# osd_carrier.net
KiCad netlist of a schematic drawn in EAGLE
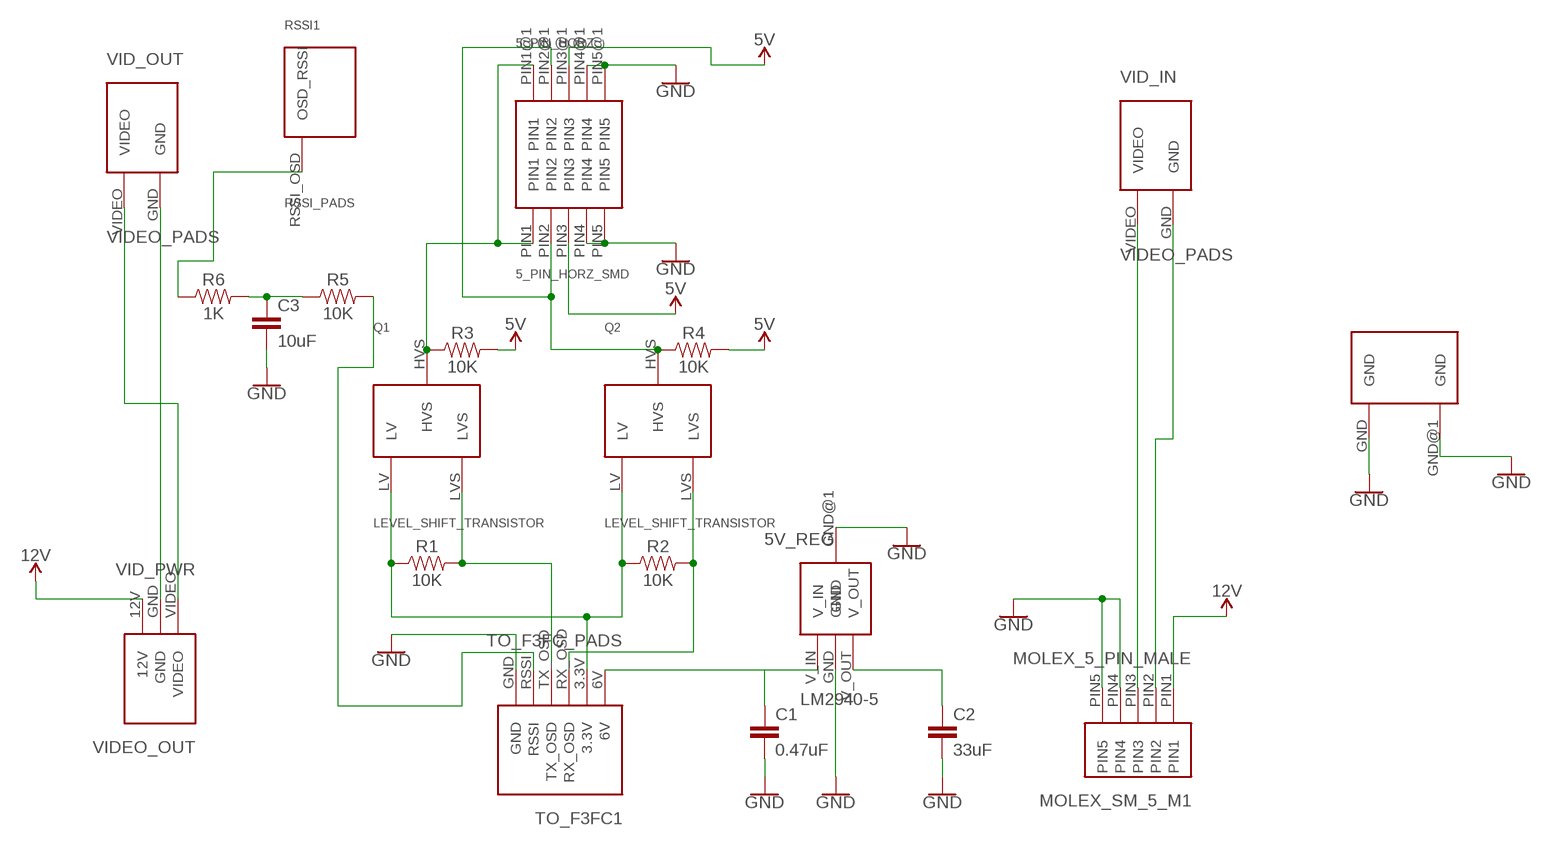
[diagram p0: schematic, sheet 1]

(export (version "E")
  (design (tool "Eeschema 10.0.6"))
  (components
    (comp (ref "5V_REG")
      (value "LM2940-5")
      (footprint "eagle-import:LM2940-5")
      (libsource (lib "eagle-import") (part "LM2940-5"))
    )
    (comp (ref "5_PIN_HORZ")
      (value "5_PIN_HORZ_SMD")
      (footprint "eagle-import:5_PIN_HORZ_SMD")
      (libsource (lib "eagle-import") (part "5_PIN_HORZ_SMD"))
    )
    (comp (ref "ANCHOR1")
      (value "ANCHOR")
      (footprint "eagle-import:ANCHOR")
      (libsource (lib "eagle-import") (part "ANCHOR"))
    )
    (comp (ref "C1")
      (value "0.47uF")
      (footprint "eagle-import:0805")
      (libsource (lib "eagle-import") (part "0.33UF/330NF-0805-50V-10%"))
    )
    (comp (ref "C2")
      (value "33uF")
      (footprint "eagle-import:0805")
      (libsource (lib "eagle-import") (part "0.33UF/330NF-0805-50V-10%"))
    )
    (comp (ref "C3")
      (value "10uF")
      (footprint "eagle-import:0805")
      (libsource (lib "eagle-import") (part "10UF-0805-10V-10%"))
    )
    (comp (ref "MOLEX_SM_5_M1")
      (value "MOLEX_5_PIN_MALE")
      (footprint "eagle-import:MOLEX_5_PIN_MALE")
      (libsource (lib "eagle-import") (part "MOLEX_5_PIN_MALE"))
    )
    (comp (ref "Q1")
      (value "LEVEL_SHIFT_TRANSISTOR")
      (footprint "eagle-import:LEVEL_SHIFT_TRANSISTOR")
      (libsource (lib "eagle-import") (part "LEVEL_SHIFT_TRANSISTOR"))
    )
    (comp (ref "Q2")
      (value "LEVEL_SHIFT_TRANSISTOR")
      (footprint "eagle-import:LEVEL_SHIFT_TRANSISTOR")
      (libsource (lib "eagle-import") (part "LEVEL_SHIFT_TRANSISTOR"))
    )
    (comp (ref "R1")
      (value "10K")
      (footprint "eagle-import:0603")
      (libsource (lib "eagle-import") (part "1OHM-0603-1/10W-1%"))
    )
    (comp (ref "R2")
      (value "10K")
      (footprint "eagle-import:0603")
      (libsource (lib "eagle-import") (part "1OHM-0603-1/10W-1%"))
    )
    (comp (ref "R3")
      (value "10K")
      (footprint "eagle-import:0603")
      (libsource (lib "eagle-import") (part "1OHM-0603-1/10W-1%"))
    )
    (comp (ref "R4")
      (value "10K")
      (footprint "eagle-import:0603")
      (libsource (lib "eagle-import") (part "1OHM-0603-1/10W-1%"))
    )
    (comp (ref "R5")
      (value "10K")
      (footprint "eagle-import:0603")
      (libsource (lib "eagle-import") (part "1OHM-0603-1/10W-1%"))
    )
    (comp (ref "R6")
      (value "1K")
      (footprint "eagle-import:0603")
      (libsource (lib "eagle-import") (part "1OHM-0603-1/10W-1%"))
    )
    (comp (ref "RSSI1")
      (value "RSSI_PADS")
      (footprint "eagle-import:RSSI_PADS")
      (libsource (lib "eagle-import") (part "RSSI_PADS"))
    )
    (comp (ref "TO_F3FC1")
      (value "TO_F3FC_PADS")
      (footprint "eagle-import:TO_F3FC_PADS")
      (libsource (lib "eagle-import") (part "TO_F3FC_PADS"))
    )
    (comp (ref "VIDEO_OUT")
      (value "VID_PWR")
      (footprint "eagle-import:VID_PWR")
      (libsource (lib "eagle-import") (part "VID_PWR"))
    )
    (comp (ref "VID_IN")
      (value "VIDEO_PADS")
      (footprint "eagle-import:VIDEO_PADS")
      (libsource (lib "eagle-import") (part "VIDEO_PADS"))
    )
    (comp (ref "VID_OUT")
      (value "VIDEO_PADS")
      (footprint "eagle-import:VIDEO_PADS")
      (libsource (lib "eagle-import") (part "VIDEO_PADS"))
    )
  )
  (nets
    (net (code "1") (name "5V") (class "Default")
      (node (ref "5V_REG") (pin "V_OUT") (pinfunction "V_OUT_V_OUT") (pintype "bidirectional"))
      (node (ref "5_PIN_HORZ") (pin "PIN3") (pinfunction "PIN3_PIN3") (pintype "bidirectional"))
      (node (ref "5_PIN_HORZ") (pin "PIN3@1") (pinfunction "PIN3_PIN3@1") (pintype "bidirectional"))
      (node (ref "C2") (pin "1") (pinfunction "1_1") (pintype "passive"))
      (node (ref "R3") (pin "2") (pinfunction "2_2") (pintype "passive"))
      (node (ref "R4") (pin "2") (pinfunction "2_2") (pintype "passive"))
    )
    (net (code "2") (name "12V") (class "Default")
      (node (ref "MOLEX_SM_5_M1") (pin "PIN1") (pinfunction "PIN1_PIN1") (pintype "bidirectional"))
      (node (ref "VIDEO_OUT") (pin "12V") (pinfunction "12V_12V") (pintype "bidirectional"))
    )
    (net (code "3") (name "GND") (class "Default")
      (node (ref "5V_REG") (pin "GND") (pinfunction "GND_GND") (pintype "bidirectional"))
      (node (ref "5V_REG") (pin "GND@1") (pinfunction "GND_GND@1") (pintype "bidirectional"))
      (node (ref "5_PIN_HORZ") (pin "PIN4") (pinfunction "PIN4_PIN4") (pintype "bidirectional"))
      (node (ref "5_PIN_HORZ") (pin "PIN4@1") (pinfunction "PIN4_PIN4@1") (pintype "bidirectional"))
      (node (ref "5_PIN_HORZ") (pin "PIN5") (pinfunction "PIN5_PIN5") (pintype "bidirectional"))
      (node (ref "5_PIN_HORZ") (pin "PIN5@1") (pinfunction "PIN5_PIN5@1") (pintype "bidirectional"))
      (node (ref "ANCHOR1") (pin "GND") (pinfunction "GND_GND") (pintype "bidirectional"))
      (node (ref "ANCHOR1") (pin "GND@1") (pinfunction "GND_GND@1") (pintype "bidirectional"))
      (node (ref "C1") (pin "2") (pinfunction "2_2") (pintype "passive"))
      (node (ref "C2") (pin "2") (pinfunction "2_2") (pintype "passive"))
      (node (ref "C3") (pin "2") (pinfunction "2_2") (pintype "passive"))
      (node (ref "MOLEX_SM_5_M1") (pin "PIN2") (pinfunction "PIN2_PIN2") (pintype "bidirectional"))
      (node (ref "MOLEX_SM_5_M1") (pin "PIN4") (pinfunction "PIN4_PIN4") (pintype "bidirectional"))
      (node (ref "MOLEX_SM_5_M1") (pin "PIN5") (pinfunction "PIN5_PIN5") (pintype "bidirectional"))
      (node (ref "TO_F3FC1") (pin "GND") (pinfunction "GND_GND") (pintype "bidirectional"))
      (node (ref "VIDEO_OUT") (pin "GND") (pinfunction "GND_GND") (pintype "bidirectional"))
      (node (ref "VID_IN") (pin "GND") (pinfunction "GND_GND") (pintype "bidirectional"))
      (node (ref "VID_OUT") (pin "GND") (pinfunction "GND_GND") (pintype "bidirectional"))
    )
    (net (code "4") (name "Net-(5V_REG-PadV_IN)") (class "Default")
      (node (ref "5V_REG") (pin "V_IN") (pinfunction "V_IN_V_IN") (pintype "bidirectional"))
      (node (ref "C1") (pin "1") (pinfunction "1_1") (pintype "passive"))
      (node (ref "TO_F3FC1") (pin "6V") (pinfunction "6V_6V") (pintype "bidirectional"))
    )
    (net (code "5") (name "Net-(5_PIN_HORZ-PIN1-PadPIN1@1)") (class "Default")
      (node (ref "5_PIN_HORZ") (pin "PIN1") (pinfunction "PIN1_PIN1") (pintype "bidirectional"))
      (node (ref "5_PIN_HORZ") (pin "PIN1@1") (pinfunction "PIN1_PIN1@1") (pintype "bidirectional"))
      (node (ref "Q1") (pin "HVS") (pinfunction "HVS_HVS") (pintype "bidirectional"))
      (node (ref "R3") (pin "1") (pinfunction "1_1") (pintype "passive"))
    )
    (net (code "6") (name "Net-(5_PIN_HORZ-PIN2-PadPIN2@1)") (class "Default")
      (node (ref "5_PIN_HORZ") (pin "PIN2") (pinfunction "PIN2_PIN2") (pintype "bidirectional"))
      (node (ref "5_PIN_HORZ") (pin "PIN2@1") (pinfunction "PIN2_PIN2@1") (pintype "bidirectional"))
      (node (ref "Q2") (pin "HVS") (pinfunction "HVS_HVS") (pintype "bidirectional"))
      (node (ref "R4") (pin "1") (pinfunction "1_1") (pintype "passive"))
    )
    (net (code "7") (name "Net-(C3-Pad1)") (class "Default")
      (node (ref "C3") (pin "1") (pinfunction "1_1") (pintype "passive"))
      (node (ref "R5") (pin "1") (pinfunction "1_1") (pintype "passive"))
      (node (ref "R6") (pin "2") (pinfunction "2_2") (pintype "passive"))
    )
    (net (code "8") (name "Net-(MOLEX_SM_5_M1-PadPIN3)") (class "Default")
      (node (ref "MOLEX_SM_5_M1") (pin "PIN3") (pinfunction "PIN3_PIN3") (pintype "bidirectional"))
      (node (ref "VID_IN") (pin "VIDEO") (pinfunction "VIDEO_VIDEO") (pintype "bidirectional"))
    )
    (net (code "9") (name "Net-(Q1-PadLV)") (class "Default")
      (node (ref "Q1") (pin "LV") (pinfunction "LV_LV") (pintype "bidirectional"))
      (node (ref "Q2") (pin "LV") (pinfunction "LV_LV") (pintype "bidirectional"))
      (node (ref "R1") (pin "1") (pinfunction "1_1") (pintype "passive"))
      (node (ref "R2") (pin "1") (pinfunction "1_1") (pintype "passive"))
      (node (ref "TO_F3FC1") (pin "3.3V") (pinfunction "3.3V_3.3V") (pintype "bidirectional"))
    )
    (net (code "10") (name "Net-(Q1-PadLVS)") (class "Default")
      (node (ref "Q1") (pin "LVS") (pinfunction "LVS_LVS") (pintype "bidirectional"))
      (node (ref "R1") (pin "2") (pinfunction "2_2") (pintype "passive"))
      (node (ref "TO_F3FC1") (pin "TX_OSD") (pinfunction "TX_OSD_TX_OSD") (pintype "bidirectional"))
    )
    (net (code "11") (name "Net-(Q2-PadLVS)") (class "Default")
      (node (ref "Q2") (pin "LVS") (pinfunction "LVS_LVS") (pintype "bidirectional"))
      (node (ref "R2") (pin "2") (pinfunction "2_2") (pintype "passive"))
      (node (ref "TO_F3FC1") (pin "RX_OSD") (pinfunction "RX_OSD_RX_OSD") (pintype "bidirectional"))
    )
    (net (code "12") (name "Net-(R5-Pad2)") (class "Default")
      (node (ref "R5") (pin "2") (pinfunction "2_2") (pintype "passive"))
      (node (ref "TO_F3FC1") (pin "RSSI") (pinfunction "RSSI_RSSI") (pintype "bidirectional"))
    )
    (net (code "13") (name "Net-(RSSI1-OSD_RSSI)") (class "Default")
      (node (ref "R6") (pin "1") (pinfunction "1_1") (pintype "passive"))
      (node (ref "RSSI1") (pin "RSSI_OSD") (pinfunction "OSD_RSSI_RSSI_OSD") (pintype "bidirectional"))
    )
    (net (code "14") (name "Net-(VIDEO_OUT-PadVIDEO)") (class "Default")
      (node (ref "VIDEO_OUT") (pin "VIDEO") (pinfunction "VIDEO_VIDEO") (pintype "bidirectional"))
      (node (ref "VID_OUT") (pin "VIDEO") (pinfunction "VIDEO_VIDEO") (pintype "bidirectional"))
    )
  )
)
